# Senior_Design_Board.net
KiCad netlist of a schematic drawn in EAGLE
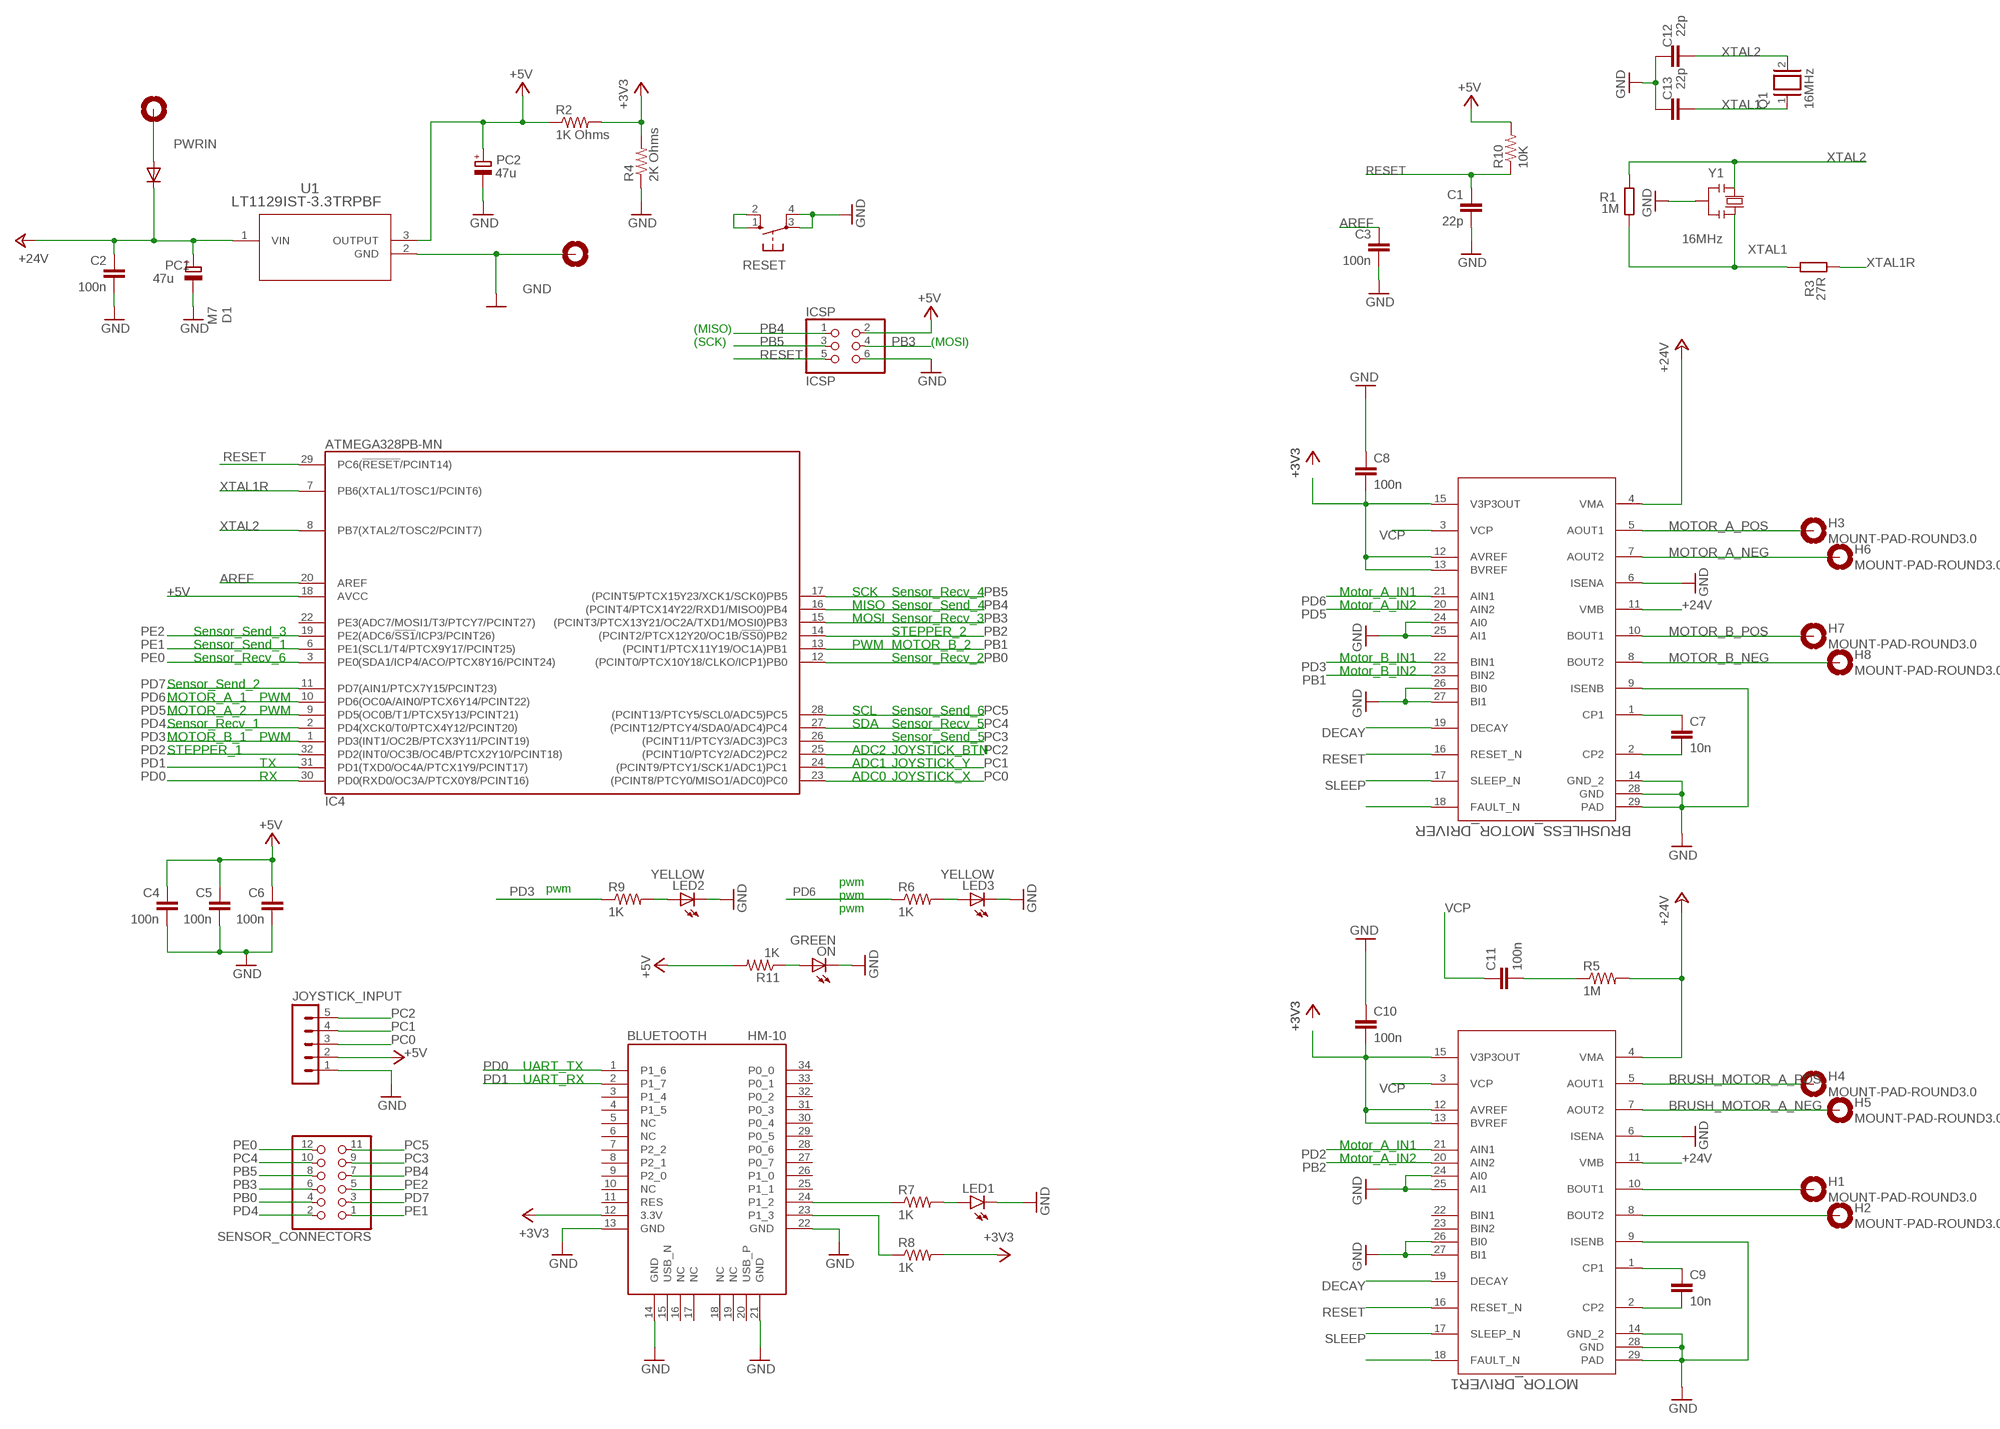
[diagram p0: schematic, sheet 1]

(export (version "E")
  (design (tool "Eeschema 10.0.6"))
  (components
    (comp (ref "BATTERY_NEG")
      (value "MOUNT-PAD-ROUND3.0")
      (footprint "eagle-import:3,0-PAD")
      (libsource (lib "eagle-import") (part "MOUNT-PAD-ROUND3.0"))
    )
    (comp (ref "BATTERY_POS")
      (value "MOUNT-PAD-ROUND3.0")
      (footprint "eagle-import:3,0-PAD")
      (libsource (lib "eagle-import") (part "MOUNT-PAD-ROUND3.0"))
    )
    (comp (ref "BLUETOOTH")
      (value "HM-10")
      (footprint "eagle-import:HM-10")
      (libsource (lib "eagle-import") (part "HM-10"))
    )
    (comp (ref "BRUSHLESS_MOTOR_DRIVER")
      (value "Value")
      (footprint "eagle-import:PWP0028C_N")
      (fields
        (field (name "ALTERNATE_PARTNUMBER") "DRV8841PWP")
        (field (name "MANUFACTURER") "Texas Instruments")
        (field (name "PARTNUMBER") "DRV8841PWPR")
      )
      (libsource (lib "eagle-import") (part "DRV8841PWP"))
    )
    (comp (ref "C1")
      (value "22p")
      (footprint "eagle-import:C0603-ROUND")
      (libsource (lib "eagle-import") (part "C-EU0603-RND"))
    )
    (comp (ref "C2")
      (value "100n")
      (footprint "eagle-import:C0603-ROUND")
      (libsource (lib "eagle-import") (part "C-EU0603-RND"))
    )
    (comp (ref "C3")
      (value "100n")
      (footprint "eagle-import:C0603-ROUND")
      (libsource (lib "eagle-import") (part "C-EU0603-RND"))
    )
    (comp (ref "C4")
      (value "100n")
      (footprint "eagle-import:C0603-ROUND")
      (libsource (lib "eagle-import") (part "C-EU0603-RND"))
    )
    (comp (ref "C5")
      (value "100n")
      (footprint "eagle-import:C0603-ROUND")
      (libsource (lib "eagle-import") (part "C-EU0603-RND"))
    )
    (comp (ref "C6")
      (value "100n")
      (footprint "eagle-import:C0603-ROUND")
      (libsource (lib "eagle-import") (part "C-EU0603-RND"))
    )
    (comp (ref "C7")
      (value "10n")
      (footprint "eagle-import:C2.5-3")
      (libsource (lib "eagle-import") (part "C2,5-3"))
    )
    (comp (ref "C8")
      (value "100n")
      (footprint "eagle-import:C2.5-3")
      (libsource (lib "eagle-import") (part "C2,5-3"))
    )
    (comp (ref "C9")
      (value "10n")
      (footprint "eagle-import:C2.5-3")
      (libsource (lib "eagle-import") (part "C2,5-3"))
    )
    (comp (ref "C10")
      (value "100n")
      (footprint "eagle-import:C2.5-3")
      (libsource (lib "eagle-import") (part "C2,5-3"))
    )
    (comp (ref "C11")
      (value "100n")
      (footprint "eagle-import:C2.5-3")
      (libsource (lib "eagle-import") (part "C2,5-3"))
    )
    (comp (ref "C12")
      (value "22p")
      (footprint "eagle-import:C0603-ROUND")
      (libsource (lib "eagle-import") (part "C-EU0603-RND"))
    )
    (comp (ref "C13")
      (value "22p")
      (footprint "eagle-import:C0603-ROUND")
      (libsource (lib "eagle-import") (part "C-EU0603-RND"))
    )
    (comp (ref "D1")
      (value "M7")
      (footprint "eagle-import:SMB")
      (libsource (lib "eagle-import") (part "DIODE-SMB"))
    )
    (comp (ref "H1")
      (value "MOUNT-PAD-ROUND3.0")
      (footprint "eagle-import:3,0-PAD")
      (libsource (lib "eagle-import") (part "MOUNT-PAD-ROUND3.0"))
    )
    (comp (ref "H2")
      (value "MOUNT-PAD-ROUND3.0")
      (footprint "eagle-import:3,0-PAD")
      (libsource (lib "eagle-import") (part "MOUNT-PAD-ROUND3.0"))
    )
    (comp (ref "H3")
      (value "MOUNT-PAD-ROUND3.0")
      (footprint "eagle-import:3,0-PAD")
      (libsource (lib "eagle-import") (part "MOUNT-PAD-ROUND3.0"))
    )
    (comp (ref "H4")
      (value "MOUNT-PAD-ROUND3.0")
      (footprint "eagle-import:3,0-PAD")
      (libsource (lib "eagle-import") (part "MOUNT-PAD-ROUND3.0"))
    )
    (comp (ref "H5")
      (value "MOUNT-PAD-ROUND3.0")
      (footprint "eagle-import:3,0-PAD")
      (libsource (lib "eagle-import") (part "MOUNT-PAD-ROUND3.0"))
    )
    (comp (ref "H6")
      (value "MOUNT-PAD-ROUND3.0")
      (footprint "eagle-import:3,0-PAD")
      (libsource (lib "eagle-import") (part "MOUNT-PAD-ROUND3.0"))
    )
    (comp (ref "H7")
      (value "MOUNT-PAD-ROUND3.0")
      (footprint "eagle-import:3,0-PAD")
      (libsource (lib "eagle-import") (part "MOUNT-PAD-ROUND3.0"))
    )
    (comp (ref "H8")
      (value "MOUNT-PAD-ROUND3.0")
      (footprint "eagle-import:3,0-PAD")
      (libsource (lib "eagle-import") (part "MOUNT-PAD-ROUND3.0"))
    )
    (comp (ref "IC4")
      (value "ATMEGA328PB-MN")
      (footprint "eagle-import:QFN32_5X5_0.50")
      (libsource (lib "eagle-import") (part "ATMEGA328PB-MN"))
    )
    (comp (ref "ICSP")
      (value "ICSP")
      (footprint "eagle-import:2X03")
      (libsource (lib "eagle-import") (part "PINHD-2X3"))
    )
    (comp (ref "JOYSTICK_INPUT")
      (value "MA05-1")
      (footprint "eagle-import:MA05-1")
      (libsource (lib "eagle-import") (part "MA05-1"))
    )
    (comp (ref "LED1")
      (value "LEDCHIP-LED0805")
      (footprint "eagle-import:CHIP-LED0805")
      (libsource (lib "eagle-import") (part "led_259_LEDCHIP-LED0805"))
    )
    (comp (ref "LED2")
      (value "YELLOW")
      (footprint "eagle-import:CHIP-LED0805")
      (libsource (lib "eagle-import") (part "LEDCHIP-LED0805"))
    )
    (comp (ref "LED3")
      (value "YELLOW")
      (footprint "eagle-import:CHIP-LED0805")
      (libsource (lib "eagle-import") (part "LEDCHIP-LED0805"))
    )
    (comp (ref "MOTOR_DRIVER1")
      (value "Value")
      (footprint "eagle-import:PWP0028C_N")
      (fields
        (field (name "ALTERNATE_PARTNUMBER") "DRV8841PWP")
        (field (name "MANUFACTURER") "Texas Instruments")
        (field (name "PARTNUMBER") "DRV8841PWPR")
      )
      (libsource (lib "eagle-import") (part "DRV8841PWP"))
    )
    (comp (ref "ON")
      (value "GREEN")
      (footprint "eagle-import:CHIP-LED0805")
      (libsource (lib "eagle-import") (part "LEDCHIP-LED0805"))
    )
    (comp (ref "PC1")
      (value "47u")
      (footprint "eagle-import:PANASONIC_D")
      (libsource (lib "eagle-import") (part "CPOL-EUD"))
    )
    (comp (ref "PC2")
      (value "47u")
      (footprint "eagle-import:PANASONIC_D")
      (libsource (lib "eagle-import") (part "CPOL-EUD"))
    )
    (comp (ref "Q1")
      (value "16MHz")
      (footprint "eagle-import:QS")
      (libsource (lib "eagle-import") (part "XTAL/S"))
    )
    (comp (ref "R1")
      (value "1M")
      (footprint "eagle-import:R0603-ROUND")
      (libsource (lib "eagle-import") (part "R-EU_R0603"))
    )
    (comp (ref "R2")
      (value "1K Ohms")
      (footprint "eagle-import:0204_7")
      (libsource (lib "eagle-import") (part "R-US_0204/7"))
    )
    (comp (ref "R3")
      (value "27R")
      (footprint "eagle-import:R0603-ROUND")
      (libsource (lib "eagle-import") (part "R-EU_R0603"))
    )
    (comp (ref "R4")
      (value "2K Ohms")
      (footprint "eagle-import:0204_7")
      (libsource (lib "eagle-import") (part "R-US_0204/7"))
    )
    (comp (ref "R5")
      (value "1M")
      (footprint "eagle-import:0204_7")
      (libsource (lib "eagle-import") (part "R-US_0204/7"))
    )
    (comp (ref "R6")
      (value "1K")
      (footprint "eagle-import:M0805")
      (libsource (lib "eagle-import") (part "R-US_M0805"))
    )
    (comp (ref "R7")
      (value "1K")
      (footprint "eagle-import:0204_7")
      (libsource (lib "eagle-import") (part "R-US_0204/7"))
    )
    (comp (ref "R8")
      (value "1K")
      (footprint "eagle-import:0204_7")
      (libsource (lib "eagle-import") (part "R-US_0204/7"))
    )
    (comp (ref "R9")
      (value "1K")
      (footprint "eagle-import:M0805")
      (libsource (lib "eagle-import") (part "R-US_M0805"))
    )
    (comp (ref "R10")
      (value "10K")
      (footprint "eagle-import:M0805")
      (libsource (lib "eagle-import") (part "R-US_M0805"))
    )
    (comp (ref "R11")
      (value "1K")
      (footprint "eagle-import:M0805")
      (libsource (lib "eagle-import") (part "R-US_M0805"))
    )
    (comp (ref "RESET")
      (value "10-XX")
      (footprint "eagle-import:B3F-10XX")
      (fields (field (name "MPN") "B3F-1000"))
      (libsource (lib "eagle-import") (part "10-XX"))
    )
    (comp (ref "SENSOR_CONNECTORS")
      (value "PINHD-2X6")
      (footprint "eagle-import:2X06")
      (libsource (lib "eagle-import") (part "PINHD-2X6"))
    )
    (comp (ref "U1")
      (value "LT1129IST-3.3TRPBF")
      (footprint "eagle-import:SOT-223_ST_LIT")
      (fields (field (name "MANUFACTURER_PART_NUMBER") "LT1129IST-3.3#TRPBF"))
      (libsource (lib "eagle-import") (part "LT1129IST-3.3TRPBF"))
    )
    (comp (ref "Y1")
      (value "16MHz")
      (footprint "eagle-import:RESONATOR")
      (libsource (lib "eagle-import") (part "RESONATORMU"))
    )
  )
  (nets
    (net (code "1") (name "+3V3") (class "Default")
      (node (ref "BLUETOOTH") (pin "12") (pinfunction "3.3V_12") (pintype "bidirectional"))
      (node (ref "R2") (pin "2") (pinfunction "2_2") (pintype "passive"))
      (node (ref "R4") (pin "2") (pinfunction "2_2") (pintype "passive"))
      (node (ref "R8") (pin "2") (pinfunction "2_2") (pintype "passive"))
    )
    (net (code "2") (name "+5V") (class "Default")
      (node (ref "C4") (pin "1") (pinfunction "1_1") (pintype "passive"))
      (node (ref "C5") (pin "1") (pinfunction "1_1") (pintype "passive"))
      (node (ref "C6") (pin "1") (pinfunction "1_1") (pintype "passive"))
      (node (ref "IC4") (pin "18") (pinfunction "AVCC_18") (pintype "power_in"))
      (node (ref "ICSP") (pin "2") (pinfunction "2_2") (pintype "passive"))
      (node (ref "JOYSTICK_INPUT") (pin "2") (pinfunction "2_2") (pintype "passive"))
      (node (ref "PC2") (pin "+") (pinfunction "+_+") (pintype "passive"))
      (node (ref "R10") (pin "2") (pinfunction "2_2") (pintype "passive"))
      (node (ref "R11") (pin "2") (pinfunction "2_2") (pintype "passive"))
      (node (ref "R2") (pin "1") (pinfunction "1_1") (pintype "passive"))
      (node (ref "U1") (pin "3") (pinfunction "OUTPUT_3") (pintype "output"))
    )
    (net (code "3") (name "+24V") (class "Default")
      (node (ref "BRUSHLESS_MOTOR_DRIVER") (pin "11") (pinfunction "VMB_11") (pintype "power_in"))
      (node (ref "BRUSHLESS_MOTOR_DRIVER") (pin "4") (pinfunction "VMA_4") (pintype "power_in"))
      (node (ref "C2") (pin "1") (pinfunction "1_1") (pintype "passive"))
      (node (ref "D1") (pin "C") (pinfunction "C_C") (pintype "passive"))
      (node (ref "MOTOR_DRIVER1") (pin "11") (pinfunction "VMB_11") (pintype "power_in"))
      (node (ref "MOTOR_DRIVER1") (pin "4") (pinfunction "VMA_4") (pintype "power_in"))
      (node (ref "PC1") (pin "+") (pinfunction "+_+") (pintype "passive"))
      (node (ref "R5") (pin "2") (pinfunction "2_2") (pintype "passive"))
      (node (ref "U1") (pin "1") (pinfunction "VIN_1") (pintype "input"))
    )
    (net (code "4") (name "/AREF") (class "Default")
      (node (ref "C3") (pin "1") (pinfunction "1_1") (pintype "passive"))
      (node (ref "IC4") (pin "20") (pinfunction "AREF_20") (pintype "passive"))
    )
    (net (code "5") (name "/BRUSH_MOTOR_A_NEG") (class "Default")
      (node (ref "H5") (pin "B3,0") (pinfunction "MOUNT_B3,0") (pintype "passive"))
      (node (ref "MOTOR_DRIVER1") (pin "7") (pinfunction "AOUT2_7") (pintype "output"))
    )
    (net (code "6") (name "/BRUSH_MOTOR_A_POS") (class "Default")
      (node (ref "H4") (pin "B3,0") (pinfunction "MOUNT_B3,0") (pintype "passive"))
      (node (ref "MOTOR_DRIVER1") (pin "5") (pinfunction "AOUT1_5") (pintype "output"))
    )
    (net (code "7") (name "/DECAY") (class "Default")
      (node (ref "BRUSHLESS_MOTOR_DRIVER") (pin "19") (pinfunction "DECAY_19") (pintype "input"))
      (node (ref "MOTOR_DRIVER1") (pin "19") (pinfunction "DECAY_19") (pintype "input"))
    )
    (net (code "8") (name "/MOTOR_A_NEG") (class "Default")
      (node (ref "BRUSHLESS_MOTOR_DRIVER") (pin "7") (pinfunction "AOUT2_7") (pintype "output"))
      (node (ref "H6") (pin "B3,0") (pinfunction "MOUNT_B3,0") (pintype "passive"))
    )
    (net (code "9") (name "/MOTOR_A_POS") (class "Default")
      (node (ref "BRUSHLESS_MOTOR_DRIVER") (pin "5") (pinfunction "AOUT1_5") (pintype "output"))
      (node (ref "H3") (pin "B3,0") (pinfunction "MOUNT_B3,0") (pintype "passive"))
    )
    (net (code "10") (name "/MOTOR_B_NEG") (class "Default")
      (node (ref "BRUSHLESS_MOTOR_DRIVER") (pin "8") (pinfunction "BOUT2_8") (pintype "output"))
      (node (ref "H8") (pin "B3,0") (pinfunction "MOUNT_B3,0") (pintype "passive"))
    )
    (net (code "11") (name "/MOTOR_B_POS") (class "Default")
      (node (ref "BRUSHLESS_MOTOR_DRIVER") (pin "10") (pinfunction "BOUT1_10") (pintype "output"))
      (node (ref "H7") (pin "B3,0") (pinfunction "MOUNT_B3,0") (pintype "passive"))
    )
    (net (code "12") (name "/PB0") (class "Default")
      (node (ref "IC4") (pin "12") (pinfunction "(PCINT0/PTCX10Y18/CLKO/ICP1)PB0_12") (pintype "bidirectional"))
      (node (ref "SENSOR_CONNECTORS") (pin "4") (pinfunction "4_4") (pintype "passive"))
    )
    (net (code "13") (name "/PB1") (class "Default")
      (node (ref "BRUSHLESS_MOTOR_DRIVER") (pin "23") (pinfunction "BIN2_23") (pintype "input"))
      (node (ref "IC4") (pin "13") (pinfunction "(PCINT1/PTCX11Y19/OC1A)PB1_13") (pintype "bidirectional"))
    )
    (net (code "14") (name "/PB2") (class "Default")
      (node (ref "IC4") (pin "14") (pinfunction "(PCINT2/PTCX12Y20/OC1B/~{SS0})PB2_14") (pintype "bidirectional"))
      (node (ref "MOTOR_DRIVER1") (pin "20") (pinfunction "AIN2_20") (pintype "input"))
    )
    (net (code "15") (name "/PB3") (class "Default")
      (node (ref "IC4") (pin "15") (pinfunction "(PCINT3/PTCX13Y21/OC2A/TXD1/MOSI0)PB3_15") (pintype "bidirectional"))
      (node (ref "ICSP") (pin "4") (pinfunction "4_4") (pintype "passive"))
      (node (ref "SENSOR_CONNECTORS") (pin "6") (pinfunction "6_6") (pintype "passive"))
    )
    (net (code "16") (name "/PB4") (class "Default")
      (node (ref "IC4") (pin "16") (pinfunction "(PCINT4/PTCX14Y22/RXD1/MISO0)PB4_16") (pintype "bidirectional"))
      (node (ref "ICSP") (pin "1") (pinfunction "1_1") (pintype "passive"))
      (node (ref "SENSOR_CONNECTORS") (pin "7") (pinfunction "7_7") (pintype "passive"))
    )
    (net (code "17") (name "/PB5") (class "Default")
      (node (ref "IC4") (pin "17") (pinfunction "(PCINT5/PTCX15Y23/XCK1/SCK0)PB5_17") (pintype "bidirectional"))
      (node (ref "ICSP") (pin "3") (pinfunction "3_3") (pintype "passive"))
      (node (ref "SENSOR_CONNECTORS") (pin "8") (pinfunction "8_8") (pintype "passive"))
    )
    (net (code "18") (name "/PC0") (class "Default")
      (node (ref "IC4") (pin "23") (pinfunction "(PCINT8/PTCY0/MISO1/ADC0)PC0_23") (pintype "bidirectional"))
      (node (ref "JOYSTICK_INPUT") (pin "3") (pinfunction "3_3") (pintype "passive"))
    )
    (net (code "19") (name "/PC1") (class "Default")
      (node (ref "IC4") (pin "24") (pinfunction "(PCINT9/PTCY1/SCK1/ADC1)PC1_24") (pintype "bidirectional"))
      (node (ref "JOYSTICK_INPUT") (pin "4") (pinfunction "4_4") (pintype "passive"))
    )
    (net (code "20") (name "/PC2") (class "Default")
      (node (ref "IC4") (pin "25") (pinfunction "(PCINT10/PTCY2/ADC2)PC2_25") (pintype "bidirectional"))
      (node (ref "JOYSTICK_INPUT") (pin "5") (pinfunction "5_5") (pintype "passive"))
    )
    (net (code "21") (name "/PC3") (class "Default")
      (node (ref "IC4") (pin "26") (pinfunction "(PCINT11/PTCY3/ADC3)PC3_26") (pintype "bidirectional"))
      (node (ref "SENSOR_CONNECTORS") (pin "9") (pinfunction "9_9") (pintype "passive"))
    )
    (net (code "22") (name "/PC4") (class "Default")
      (node (ref "IC4") (pin "27") (pinfunction "(PCINT12/PTCY4/SDA0/ADC4)PC4_27") (pintype "bidirectional"))
      (node (ref "SENSOR_CONNECTORS") (pin "10") (pinfunction "10_10") (pintype "passive"))
    )
    (net (code "23") (name "/PC5") (class "Default")
      (node (ref "IC4") (pin "28") (pinfunction "(PCINT13/PTCY5/SCL0/ADC5)PC5_28") (pintype "bidirectional"))
      (node (ref "SENSOR_CONNECTORS") (pin "11") (pinfunction "11_11") (pintype "passive"))
    )
    (net (code "24") (name "/PD0") (class "Default")
      (node (ref "BLUETOOTH") (pin "1") (pinfunction "P1_6_1") (pintype "bidirectional"))
      (node (ref "IC4") (pin "30") (pinfunction "PD0(RXD0/OC3A/PTCX0Y8/PCINT16)_30") (pintype "bidirectional"))
    )
    (net (code "25") (name "/PD1") (class "Default")
      (node (ref "BLUETOOTH") (pin "2") (pinfunction "P1_7_2") (pintype "bidirectional"))
      (node (ref "IC4") (pin "31") (pinfunction "PD1(TXD0/OC4A/PTCX1Y9/PCINT17)_31") (pintype "bidirectional"))
    )
    (net (code "26") (name "/PD2") (class "Default")
      (node (ref "IC4") (pin "32") (pinfunction "PD2(INT0/OC3B/OC4B/PTCX2Y10/PCINT18)_32") (pintype "bidirectional"))
      (node (ref "MOTOR_DRIVER1") (pin "21") (pinfunction "AIN1_21") (pintype "input"))
    )
    (net (code "27") (name "/PD3") (class "Default")
      (node (ref "BRUSHLESS_MOTOR_DRIVER") (pin "22") (pinfunction "BIN1_22") (pintype "input"))
      (node (ref "IC4") (pin "1") (pinfunction "PD3(INT1/OC2B/PTCX3Y11/PCINT19)_1") (pintype "bidirectional"))
      (node (ref "R9") (pin "1") (pinfunction "1_1") (pintype "passive"))
    )
    (net (code "28") (name "/PD4") (class "Default")
      (node (ref "IC4") (pin "2") (pinfunction "PD4(XCK0/T0/PTCX4Y12/PCINT20)_2") (pintype "bidirectional"))
      (node (ref "SENSOR_CONNECTORS") (pin "2") (pinfunction "2_2") (pintype "passive"))
    )
    (net (code "29") (name "/PD5") (class "Default")
      (node (ref "BRUSHLESS_MOTOR_DRIVER") (pin "20") (pinfunction "AIN2_20") (pintype "input"))
      (node (ref "IC4") (pin "9") (pinfunction "PD5(OC0B/T1/PTCX5Y13/PCINT21)_9") (pintype "bidirectional"))
    )
    (net (code "30") (name "/PD6") (class "Default")
      (node (ref "BRUSHLESS_MOTOR_DRIVER") (pin "21") (pinfunction "AIN1_21") (pintype "input"))
      (node (ref "IC4") (pin "10") (pinfunction "PD6(OC0A/AIN0/PTCX6Y14/PCINT22)_10") (pintype "bidirectional"))
      (node (ref "R6") (pin "1") (pinfunction "1_1") (pintype "passive"))
    )
    (net (code "31") (name "/PD7") (class "Default")
      (node (ref "IC4") (pin "11") (pinfunction "PD7(AIN1/PTCX7Y15/PCINT23)_11") (pintype "bidirectional"))
      (node (ref "SENSOR_CONNECTORS") (pin "3") (pinfunction "3_3") (pintype "passive"))
    )
    (net (code "32") (name "/PE0") (class "Default")
      (node (ref "IC4") (pin "3") (pinfunction "PE0(SDA1/ICP4/ACO/PTCX8Y16/PCINT24)_3") (pintype "bidirectional"))
      (node (ref "SENSOR_CONNECTORS") (pin "12") (pinfunction "12_12") (pintype "passive"))
    )
    (net (code "33") (name "/PE1") (class "Default")
      (node (ref "IC4") (pin "6") (pinfunction "PE1(SCL1/T4/PTCX9Y17/PCINT25)_6") (pintype "bidirectional"))
      (node (ref "SENSOR_CONNECTORS") (pin "1") (pinfunction "1_1") (pintype "passive"))
    )
    (net (code "34") (name "/PE2") (class "Default")
      (node (ref "IC4") (pin "19") (pinfunction "PE2(ADC6/~{SS1}/ICP3/PCINT26)_19") (pintype "bidirectional"))
      (node (ref "SENSOR_CONNECTORS") (pin "5") (pinfunction "5_5") (pintype "passive"))
    )
    (net (code "35") (name "/PWRIN") (class "Default")
      (node (ref "BATTERY_NEG") (pin "B3,0") (pinfunction "MOUNT_B3,0") (pintype "passive"))
      (node (ref "D1") (pin "A") (pinfunction "A_A") (pintype "passive"))
    )
    (net (code "36") (name "/RESET") (class "Default")
      (node (ref "BRUSHLESS_MOTOR_DRIVER") (pin "16") (pinfunction "RESET_N_16") (pintype "input"))
      (node (ref "C1") (pin "1") (pinfunction "1_1") (pintype "passive"))
      (node (ref "IC4") (pin "29") (pinfunction "PC6(~{RESET}/PCINT14)_29") (pintype "bidirectional"))
      (node (ref "ICSP") (pin "5") (pinfunction "5_5") (pintype "passive"))
      (node (ref "MOTOR_DRIVER1") (pin "16") (pinfunction "RESET_N_16") (pintype "input"))
      (node (ref "R10") (pin "1") (pinfunction "1_1") (pintype "passive"))
      (node (ref "RESET") (pin "1") (pinfunction "S_1") (pintype "passive"))
      (node (ref "RESET") (pin "2") (pinfunction "S1_2") (pintype "passive"))
    )
    (net (code "37") (name "/SLEEP") (class "Default")
      (node (ref "BRUSHLESS_MOTOR_DRIVER") (pin "17") (pinfunction "SLEEP_N_17") (pintype "input"))
      (node (ref "MOTOR_DRIVER1") (pin "17") (pinfunction "SLEEP_N_17") (pintype "input"))
    )
    (net (code "38") (name "/VCP") (class "Default")
      (node (ref "BRUSHLESS_MOTOR_DRIVER") (pin "3") (pinfunction "VCP_3") (pintype "power_in"))
      (node (ref "C11") (pin "1") (pinfunction "1_1") (pintype "passive"))
      (node (ref "MOTOR_DRIVER1") (pin "3") (pinfunction "VCP_3") (pintype "power_in"))
    )
    (net (code "39") (name "/XTAL1") (class "Default")
      (node (ref "C13") (pin "1") (pinfunction "1_1") (pintype "passive"))
      (node (ref "Q1") (pin "1") (pinfunction "1_1") (pintype "passive"))
      (node (ref "R1") (pin "1") (pinfunction "1_1") (pintype "passive"))
      (node (ref "R3") (pin "2") (pinfunction "2_2") (pintype "passive"))
      (node (ref "Y1") (pin "3") (pinfunction "3_3") (pintype "passive"))
    )
    (net (code "40") (name "/XTAL1R") (class "Default")
      (node (ref "IC4") (pin "7") (pinfunction "PB6(XTAL1/TOSC1/PCINT6)_7") (pintype "bidirectional"))
      (node (ref "R3") (pin "1") (pinfunction "1_1") (pintype "passive"))
    )
    (net (code "41") (name "/XTAL2") (class "Default")
      (node (ref "C12") (pin "1") (pinfunction "1_1") (pintype "passive"))
      (node (ref "IC4") (pin "8") (pinfunction "PB7(XTAL2/TOSC2/PCINT7)_8") (pintype "bidirectional"))
      (node (ref "Q1") (pin "2") (pinfunction "2_2") (pintype "passive"))
      (node (ref "R1") (pin "2") (pinfunction "2_2") (pintype "passive"))
      (node (ref "Y1") (pin "1") (pinfunction "1_1") (pintype "passive"))
    )
    (net (code "42") (name "GND") (class "Default")
      (node (ref "BATTERY_POS") (pin "B3,0") (pinfunction "MOUNT_B3,0") (pintype "passive"))
      (node (ref "BLUETOOTH") (pin "13") (pinfunction "GND_13") (pintype "bidirectional"))
      (node (ref "BLUETOOTH") (pin "14") (pinfunction "GND_14") (pintype "bidirectional"))
      (node (ref "BLUETOOTH") (pin "21") (pinfunction "GND_21") (pintype "bidirectional"))
      (node (ref "BLUETOOTH") (pin "22") (pinfunction "GND_22") (pintype "bidirectional"))
      (node (ref "BRUSHLESS_MOTOR_DRIVER") (pin "14") (pinfunction "GND_2_14") (pintype "power_in"))
      (node (ref "BRUSHLESS_MOTOR_DRIVER") (pin "24") (pinfunction "AI0_24") (pintype "input"))
      (node (ref "BRUSHLESS_MOTOR_DRIVER") (pin "25") (pinfunction "AI1_25") (pintype "input"))
      (node (ref "BRUSHLESS_MOTOR_DRIVER") (pin "26") (pinfunction "BI0_26") (pintype "input"))
      (node (ref "BRUSHLESS_MOTOR_DRIVER") (pin "27") (pinfunction "BI1_27") (pintype "input"))
      (node (ref "BRUSHLESS_MOTOR_DRIVER") (pin "28") (pinfunction "GND_28") (pintype "power_in"))
      (node (ref "BRUSHLESS_MOTOR_DRIVER") (pin "29") (pinfunction "PAD_29") (pintype "power_in"))
      (node (ref "BRUSHLESS_MOTOR_DRIVER") (pin "6") (pinfunction "ISENA_6") (pintype "bidirectional"))
      (node (ref "BRUSHLESS_MOTOR_DRIVER") (pin "9") (pinfunction "ISENB_9") (pintype "bidirectional"))
      (node (ref "C1") (pin "2") (pinfunction "2_2") (pintype "passive"))
      (node (ref "C10") (pin "1") (pinfunction "1_1") (pintype "passive"))
      (node (ref "C12") (pin "2") (pinfunction "2_2") (pintype "passive"))
      (node (ref "C13") (pin "2") (pinfunction "2_2") (pintype "passive"))
      (node (ref "C2") (pin "2") (pinfunction "2_2") (pintype "passive"))
      (node (ref "C3") (pin "2") (pinfunction "2_2") (pintype "passive"))
      (node (ref "C4") (pin "2") (pinfunction "2_2") (pintype "passive"))
      (node (ref "C5") (pin "2") (pinfunction "2_2") (pintype "passive"))
      (node (ref "C6") (pin "2") (pinfunction "2_2") (pintype "passive"))
      (node (ref "C8") (pin "1") (pinfunction "1_1") (pintype "passive"))
      (node (ref "ICSP") (pin "6") (pinfunction "6_6") (pintype "passive"))
      (node (ref "JOYSTICK_INPUT") (pin "1") (pinfunction "1_1") (pintype "passive"))
      (node (ref "LED1") (pin "C") (pinfunction "C_C") (pintype "passive"))
      (node (ref "LED2") (pin "C") (pinfunction "C_C") (pintype "passive"))
      (node (ref "LED3") (pin "C") (pinfunction "C_C") (pintype "passive"))
      (node (ref "MOTOR_DRIVER1") (pin "14") (pinfunction "GND_2_14") (pintype "power_in"))
      (node (ref "MOTOR_DRIVER1") (pin "24") (pinfunction "AI0_24") (pintype "input"))
      (node (ref "MOTOR_DRIVER1") (pin "25") (pinfunction "AI1_25") (pintype "input"))
      (node (ref "MOTOR_DRIVER1") (pin "26") (pinfunction "BI0_26") (pintype "input"))
      (node (ref "MOTOR_DRIVER1") (pin "27") (pinfunction "BI1_27") (pintype "input"))
      (node (ref "MOTOR_DRIVER1") (pin "28") (pinfunction "GND_28") (pintype "power_in"))
      (node (ref "MOTOR_DRIVER1") (pin "29") (pinfunction "PAD_29") (pintype "power_in"))
      (node (ref "MOTOR_DRIVER1") (pin "6") (pinfunction "ISENA_6") (pintype "bidirectional"))
      (node (ref "MOTOR_DRIVER1") (pin "9") (pinfunction "ISENB_9") (pintype "bidirectional"))
      (node (ref "ON") (pin "C") (pinfunction "C_C") (pintype "passive"))
      (node (ref "PC1") (pin "-") (pinfunction "-_-") (pintype "passive"))
      (node (ref "PC2") (pin "-") (pinfunction "-_-") (pintype "passive"))
      (node (ref "R4") (pin "1") (pinfunction "1_1") (pintype "passive"))
      (node (ref "RESET") (pin "3") (pinfunction "P_3") (pintype "passive"))
      (node (ref "RESET") (pin "4") (pinfunction "P1_4") (pintype "passive"))
      (node (ref "U1") (pin "2") (pinfunction "GND_2") (pintype "power_in"))
      (node (ref "Y1") (pin "2") (pinfunction "2_2") (pintype "passive"))
    )
    (net (code "43") (name "Net-(BLUETOOTH-P1_2)") (class "Default")
      (node (ref "BLUETOOTH") (pin "24") (pinfunction "P1_2_24") (pintype "bidirectional"))
      (node (ref "R7") (pin "1") (pinfunction "1_1") (pintype "passive"))
    )
    (net (code "44") (name "Net-(BLUETOOTH-P1_3)") (class "Default")
      (node (ref "BLUETOOTH") (pin "23") (pinfunction "P1_3_23") (pintype "bidirectional"))
      (node (ref "R8") (pin "1") (pinfunction "1_1") (pintype "passive"))
    )
    (net (code "45") (name "Net-(BRUSHLESS_MOTOR_DRIVER-AVREF)") (class "Default")
      (node (ref "BRUSHLESS_MOTOR_DRIVER") (pin "12") (pinfunction "AVREF_12") (pintype "input"))
      (node (ref "BRUSHLESS_MOTOR_DRIVER") (pin "13") (pinfunction "BVREF_13") (pintype "input"))
      (node (ref "BRUSHLESS_MOTOR_DRIVER") (pin "15") (pinfunction "V3P3OUT_15") (pintype "power_in"))
      (node (ref "C8") (pin "2") (pinfunction "2_2") (pintype "passive"))
    )
    (net (code "46") (name "Net-(BRUSHLESS_MOTOR_DRIVER-CP1)") (class "Default")
      (node (ref "BRUSHLESS_MOTOR_DRIVER") (pin "1") (pinfunction "CP1_1") (pintype "passive"))
      (node (ref "C7") (pin "1") (pinfunction "1_1") (pintype "passive"))
    )
    (net (code "47") (name "Net-(BRUSHLESS_MOTOR_DRIVER-CP2)") (class "Default")
      (node (ref "BRUSHLESS_MOTOR_DRIVER") (pin "2") (pinfunction "CP2_2") (pintype "passive"))
      (node (ref "C7") (pin "2") (pinfunction "2_2") (pintype "passive"))
    )
    (net (code "48") (name "Net-(C11-Pad2)") (class "Default")
      (node (ref "C11") (pin "2") (pinfunction "2_2") (pintype "passive"))
      (node (ref "R5") (pin "1") (pinfunction "1_1") (pintype "passive"))
    )
    (net (code "49") (name "Net-(H1-MOUNT)") (class "Default")
      (node (ref "H1") (pin "B3,0") (pinfunction "MOUNT_B3,0") (pintype "passive"))
      (node (ref "MOTOR_DRIVER1") (pin "10") (pinfunction "BOUT1_10") (pintype "output"))
    )
    (net (code "50") (name "Net-(H2-MOUNT)") (class "Default")
      (node (ref "H2") (pin "B3,0") (pinfunction "MOUNT_B3,0") (pintype "passive"))
      (node (ref "MOTOR_DRIVER1") (pin "8") (pinfunction "BOUT2_8") (pintype "output"))
    )
    (net (code "51") (name "Net-(LED1-PadA)") (class "Default")
      (node (ref "LED1") (pin "A") (pinfunction "A_A") (pintype "passive"))
      (node (ref "R7") (pin "2") (pinfunction "2_2") (pintype "passive"))
    )
    (net (code "52") (name "Net-(LED2-PadA)") (class "Default")
      (node (ref "LED2") (pin "A") (pinfunction "A_A") (pintype "passive"))
      (node (ref "R9") (pin "2") (pinfunction "2_2") (pintype "passive"))
    )
    (net (code "53") (name "Net-(LED3-PadA)") (class "Default")
      (node (ref "LED3") (pin "A") (pinfunction "A_A") (pintype "passive"))
      (node (ref "R6") (pin "2") (pinfunction "2_2") (pintype "passive"))
    )
    (net (code "54") (name "Net-(MOTOR_DRIVER1-AVREF)") (class "Default")
      (node (ref "C10") (pin "2") (pinfunction "2_2") (pintype "passive"))
      (node (ref "MOTOR_DRIVER1") (pin "12") (pinfunction "AVREF_12") (pintype "input"))
      (node (ref "MOTOR_DRIVER1") (pin "13") (pinfunction "BVREF_13") (pintype "input"))
      (node (ref "MOTOR_DRIVER1") (pin "15") (pinfunction "V3P3OUT_15") (pintype "power_in"))
    )
    (net (code "55") (name "Net-(MOTOR_DRIVER1-CP1)") (class "Default")
      (node (ref "C9") (pin "1") (pinfunction "1_1") (pintype "passive"))
      (node (ref "MOTOR_DRIVER1") (pin "1") (pinfunction "CP1_1") (pintype "passive"))
    )
    (net (code "56") (name "Net-(MOTOR_DRIVER1-CP2)") (class "Default")
      (node (ref "C9") (pin "2") (pinfunction "2_2") (pintype "passive"))
      (node (ref "MOTOR_DRIVER1") (pin "2") (pinfunction "CP2_2") (pintype "passive"))
    )
    (net (code "57") (name "Net-(ON-PadA)") (class "Default")
      (node (ref "ON") (pin "A") (pinfunction "A_A") (pintype "passive"))
      (node (ref "R11") (pin "1") (pinfunction "1_1") (pintype "passive"))
    )
    (net (code "58") (name "unconnected-(BLUETOOTH-NC-Pad5)") (class "Default")
      (node (ref "BLUETOOTH") (pin "5") (pinfunction "NC_5") (pintype "bidirectional"))
    )
    (net (code "59") (name "unconnected-(BLUETOOTH-NC-Pad6)") (class "Default")
      (node (ref "BLUETOOTH") (pin "6") (pinfunction "NC_6") (pintype "bidirectional"))
    )
    (net (code "60") (name "unconnected-(BLUETOOTH-NC-Pad10)") (class "Default")
      (node (ref "BLUETOOTH") (pin "10") (pinfunction "NC_10") (pintype "bidirectional"))
    )
    (net (code "61") (name "unconnected-(BLUETOOTH-NC-Pad16)") (class "Default")
      (node (ref "BLUETOOTH") (pin "16") (pinfunction "NC_16") (pintype "bidirectional"))
    )
    (net (code "62") (name "unconnected-(BLUETOOTH-NC-Pad17)") (class "Default")
      (node (ref "BLUETOOTH") (pin "17") (pinfunction "NC_17") (pintype "bidirectional"))
    )
    (net (code "63") (name "unconnected-(BLUETOOTH-NC-Pad18)") (class "Default")
      (node (ref "BLUETOOTH") (pin "18") (pinfunction "NC_18") (pintype "bidirectional"))
    )
    (net (code "64") (name "unconnected-(BLUETOOTH-NC-Pad19)") (class "Default")
      (node (ref "BLUETOOTH") (pin "19") (pinfunction "NC_19") (pintype "bidirectional"))
    )
    (net (code "65") (name "unconnected-(BLUETOOTH-P0_0-Pad34)") (class "Default")
      (node (ref "BLUETOOTH") (pin "34") (pinfunction "P0_0_34") (pintype "bidirectional"))
    )
    (net (code "66") (name "unconnected-(BLUETOOTH-P0_1-Pad33)") (class "Default")
      (node (ref "BLUETOOTH") (pin "33") (pinfunction "P0_1_33") (pintype "bidirectional"))
    )
    (net (code "67") (name "unconnected-(BLUETOOTH-P0_2-Pad32)") (class "Default")
      (node (ref "BLUETOOTH") (pin "32") (pinfunction "P0_2_32") (pintype "bidirectional"))
    )
    (net (code "68") (name "unconnected-(BLUETOOTH-P0_3-Pad31)") (class "Default")
      (node (ref "BLUETOOTH") (pin "31") (pinfunction "P0_3_31") (pintype "bidirectional"))
    )
    (net (code "69") (name "unconnected-(BLUETOOTH-P0_4-Pad30)") (class "Default")
      (node (ref "BLUETOOTH") (pin "30") (pinfunction "P0_4_30") (pintype "bidirectional"))
    )
    (net (code "70") (name "unconnected-(BLUETOOTH-P0_5-Pad29)") (class "Default")
      (node (ref "BLUETOOTH") (pin "29") (pinfunction "P0_5_29") (pintype "bidirectional"))
    )
    (net (code "71") (name "unconnected-(BLUETOOTH-P0_6-Pad28)") (class "Default")
      (node (ref "BLUETOOTH") (pin "28") (pinfunction "P0_6_28") (pintype "bidirectional"))
    )
    (net (code "72") (name "unconnected-(BLUETOOTH-P0_7-Pad27)") (class "Default")
      (node (ref "BLUETOOTH") (pin "27") (pinfunction "P0_7_27") (pintype "bidirectional"))
    )
    (net (code "73") (name "unconnected-(BLUETOOTH-P1_0-Pad26)") (class "Default")
      (node (ref "BLUETOOTH") (pin "26") (pinfunction "P1_0_26") (pintype "bidirectional"))
    )
    (net (code "74") (name "unconnected-(BLUETOOTH-P1_1-Pad25)") (class "Default")
      (node (ref "BLUETOOTH") (pin "25") (pinfunction "P1_1_25") (pintype "bidirectional"))
    )
    (net (code "75") (name "unconnected-(BLUETOOTH-P1_4-Pad3)") (class "Default")
      (node (ref "BLUETOOTH") (pin "3") (pinfunction "P1_4_3") (pintype "bidirectional"))
    )
    (net (code "76") (name "unconnected-(BLUETOOTH-P1_5-Pad4)") (class "Default")
      (node (ref "BLUETOOTH") (pin "4") (pinfunction "P1_5_4") (pintype "bidirectional"))
    )
    (net (code "77") (name "unconnected-(BLUETOOTH-P2_0-Pad9)") (class "Default")
      (node (ref "BLUETOOTH") (pin "9") (pinfunction "P2_0_9") (pintype "bidirectional"))
    )
    (net (code "78") (name "unconnected-(BLUETOOTH-P2_1-Pad8)") (class "Default")
      (node (ref "BLUETOOTH") (pin "8") (pinfunction "P2_1_8") (pintype "bidirectional"))
    )
    (net (code "79") (name "unconnected-(BLUETOOTH-P2_2-Pad7)") (class "Default")
      (node (ref "BLUETOOTH") (pin "7") (pinfunction "P2_2_7") (pintype "bidirectional"))
    )
    (net (code "80") (name "unconnected-(BLUETOOTH-RES-Pad11)") (class "Default")
      (node (ref "BLUETOOTH") (pin "11") (pinfunction "RES_11") (pintype "bidirectional"))
    )
    (net (code "81") (name "unconnected-(BLUETOOTH-USB_N-Pad15)") (class "Default")
      (node (ref "BLUETOOTH") (pin "15") (pinfunction "USB_N_15") (pintype "bidirectional"))
    )
    (net (code "82") (name "unconnected-(BLUETOOTH-USB_P-Pad20)") (class "Default")
      (node (ref "BLUETOOTH") (pin "20") (pinfunction "USB_P_20") (pintype "bidirectional"))
    )
    (net (code "83") (name "unconnected-(BRUSHLESS_MOTOR_DRIVER-FAULT_N-Pad18)") (class "Default")
      (node (ref "BRUSHLESS_MOTOR_DRIVER") (pin "18") (pinfunction "FAULT_N_18") (pintype "open_collector"))
    )
    (net (code "84") (name "unconnected-(IC4A-PE3(ADC7{slash}MOSI1{slash}T3{slash}PTCY7{slash}PCINT27)-Pad22)") (class "Default")
      (node (ref "IC4") (pin "22") (pinfunction "PE3(ADC7/MOSI1/T3/PTCY7/PCINT27)_22") (pintype "bidirectional"))
    )
    (net (code "85") (name "unconnected-(MOTOR_DRIVER1-BIN1-Pad22)") (class "Default")
      (node (ref "MOTOR_DRIVER1") (pin "22") (pinfunction "BIN1_22") (pintype "input"))
    )
    (net (code "86") (name "unconnected-(MOTOR_DRIVER1-BIN2-Pad23)") (class "Default")
      (node (ref "MOTOR_DRIVER1") (pin "23") (pinfunction "BIN2_23") (pintype "input"))
    )
    (net (code "87") (name "unconnected-(MOTOR_DRIVER1-FAULT_N-Pad18)") (class "Default")
      (node (ref "MOTOR_DRIVER1") (pin "18") (pinfunction "FAULT_N_18") (pintype "open_collector"))
    )
  )
)
